# athf-er-acrylic.net
KiCad netlist of a schematic drawn in EAGLE
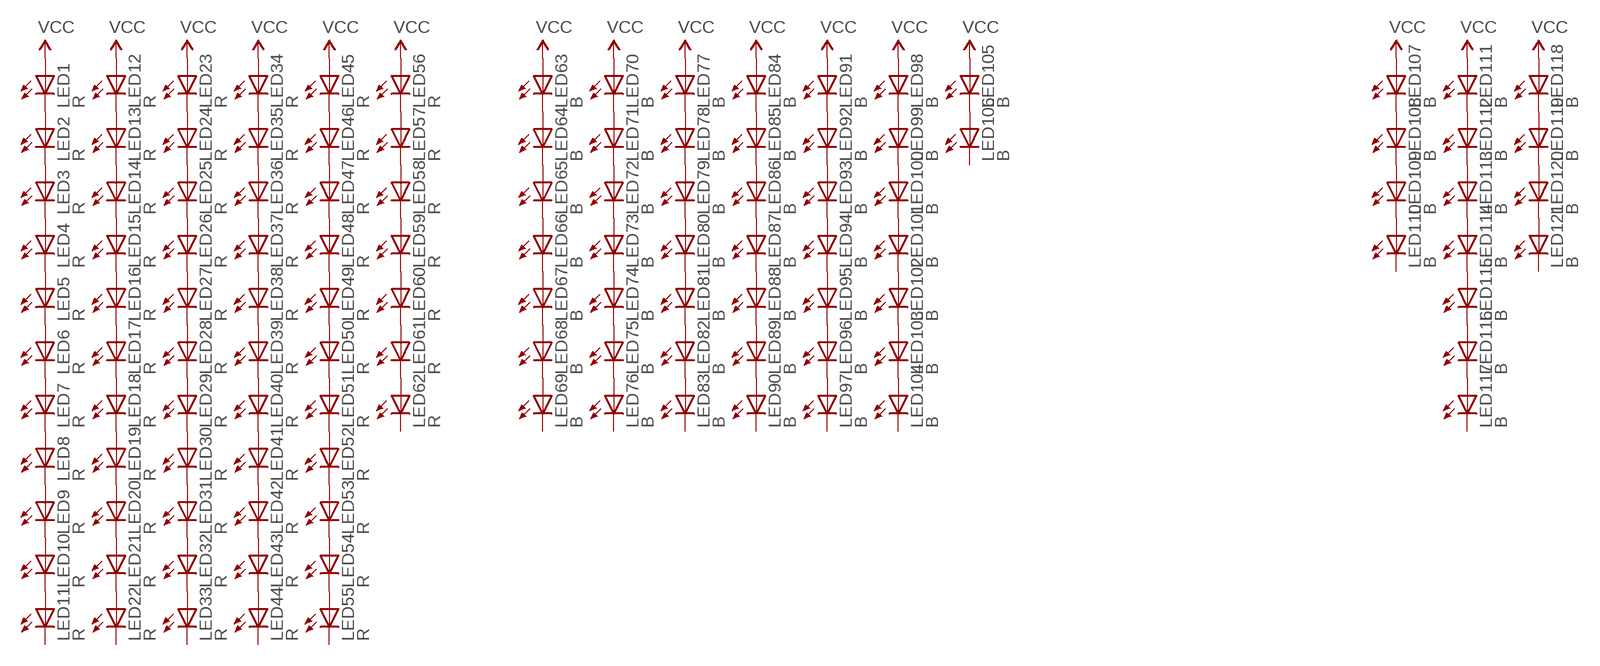
[diagram p0: schematic, sheet 1]

(export (version "E")
  (design (tool "Eeschema 10.0.6"))
  (components
    (comp (ref "LED1")
      (value "R")
      (footprint "eagle-import:LED5MMSQUARE")
      (libsource (lib "eagle-import") (part "LEDLED5MMSQUARE"))
    )
    (comp (ref "LED2")
      (value "R")
      (footprint "eagle-import:LED5MMSQUARE")
      (libsource (lib "eagle-import") (part "LEDLED5MMSQUARE"))
    )
    (comp (ref "LED3")
      (value "R")
      (footprint "eagle-import:LED5MMSQUARE")
      (libsource (lib "eagle-import") (part "LEDLED5MMSQUARE"))
    )
    (comp (ref "LED4")
      (value "R")
      (footprint "eagle-import:LED5MMSQUARE")
      (libsource (lib "eagle-import") (part "LEDLED5MMSQUARE"))
    )
    (comp (ref "LED5")
      (value "R")
      (footprint "eagle-import:LED5MMSQUARE")
      (libsource (lib "eagle-import") (part "LEDLED5MMSQUARE"))
    )
    (comp (ref "LED6")
      (value "R")
      (footprint "eagle-import:LED5MMSQUARE")
      (libsource (lib "eagle-import") (part "LEDLED5MMSQUARE"))
    )
    (comp (ref "LED7")
      (value "R")
      (footprint "eagle-import:LED5MMSQUARE")
      (libsource (lib "eagle-import") (part "LEDLED5MMSQUARE"))
    )
    (comp (ref "LED8")
      (value "R")
      (footprint "eagle-import:LED5MMSQUARE")
      (libsource (lib "eagle-import") (part "LEDLED5MMSQUARE"))
    )
    (comp (ref "LED9")
      (value "R")
      (footprint "eagle-import:LED5MMSQUARE")
      (libsource (lib "eagle-import") (part "LEDLED5MMSQUARE"))
    )
    (comp (ref "LED10")
      (value "R")
      (footprint "eagle-import:LED5MMSQUARE")
      (libsource (lib "eagle-import") (part "LEDLED5MMSQUARE"))
    )
    (comp (ref "LED11")
      (value "R")
      (footprint "eagle-import:LED5MMSQUARE")
      (libsource (lib "eagle-import") (part "LEDLED5MMSQUARE"))
    )
    (comp (ref "LED12")
      (value "R")
      (footprint "eagle-import:LED5MMSQUARE")
      (libsource (lib "eagle-import") (part "LEDLED5MMSQUARE"))
    )
    (comp (ref "LED13")
      (value "R")
      (footprint "eagle-import:LED5MMSQUARE")
      (libsource (lib "eagle-import") (part "LEDLED5MMSQUARE"))
    )
    (comp (ref "LED14")
      (value "R")
      (footprint "eagle-import:LED5MMSQUARE")
      (libsource (lib "eagle-import") (part "LEDLED5MMSQUARE"))
    )
    (comp (ref "LED15")
      (value "R")
      (footprint "eagle-import:LED5MMSQUARE")
      (libsource (lib "eagle-import") (part "LEDLED5MMSQUARE"))
    )
    (comp (ref "LED16")
      (value "R")
      (footprint "eagle-import:LED5MMSQUARE")
      (libsource (lib "eagle-import") (part "LEDLED5MMSQUARE"))
    )
    (comp (ref "LED17")
      (value "R")
      (footprint "eagle-import:LED5MMSQUARE")
      (libsource (lib "eagle-import") (part "LEDLED5MMSQUARE"))
    )
    (comp (ref "LED18")
      (value "R")
      (footprint "eagle-import:LED5MMSQUARE")
      (libsource (lib "eagle-import") (part "LEDLED5MMSQUARE"))
    )
    (comp (ref "LED19")
      (value "R")
      (footprint "eagle-import:LED5MMSQUARE")
      (libsource (lib "eagle-import") (part "LEDLED5MMSQUARE"))
    )
    (comp (ref "LED20")
      (value "R")
      (footprint "eagle-import:LED5MMSQUARE")
      (libsource (lib "eagle-import") (part "LEDLED5MMSQUARE"))
    )
    (comp (ref "LED21")
      (value "R")
      (footprint "eagle-import:LED5MMSQUARE")
      (libsource (lib "eagle-import") (part "LEDLED5MMSQUARE"))
    )
    (comp (ref "LED22")
      (value "R")
      (footprint "eagle-import:LED5MMSQUARE")
      (libsource (lib "eagle-import") (part "LEDLED5MMSQUARE"))
    )
    (comp (ref "LED23")
      (value "R")
      (footprint "eagle-import:LED5MMSQUARE")
      (libsource (lib "eagle-import") (part "LEDLED5MMSQUARE"))
    )
    (comp (ref "LED24")
      (value "R")
      (footprint "eagle-import:LED5MMSQUARE")
      (libsource (lib "eagle-import") (part "LEDLED5MMSQUARE"))
    )
    (comp (ref "LED25")
      (value "R")
      (footprint "eagle-import:LED5MMSQUARE")
      (libsource (lib "eagle-import") (part "LEDLED5MMSQUARE"))
    )
    (comp (ref "LED26")
      (value "R")
      (footprint "eagle-import:LED5MMSQUARE")
      (libsource (lib "eagle-import") (part "LEDLED5MMSQUARE"))
    )
    (comp (ref "LED27")
      (value "R")
      (footprint "eagle-import:LED5MMSQUARE")
      (libsource (lib "eagle-import") (part "LEDLED5MMSQUARE"))
    )
    (comp (ref "LED28")
      (value "R")
      (footprint "eagle-import:LED5MMSQUARE")
      (libsource (lib "eagle-import") (part "LEDLED5MMSQUARE"))
    )
    (comp (ref "LED29")
      (value "R")
      (footprint "eagle-import:LED5MMSQUARE")
      (libsource (lib "eagle-import") (part "LEDLED5MMSQUARE"))
    )
    (comp (ref "LED30")
      (value "R")
      (footprint "eagle-import:LED5MMSQUARE")
      (libsource (lib "eagle-import") (part "LEDLED5MMSQUARE"))
    )
    (comp (ref "LED31")
      (value "R")
      (footprint "eagle-import:LED5MMSQUARE")
      (libsource (lib "eagle-import") (part "LEDLED5MMSQUARE"))
    )
    (comp (ref "LED32")
      (value "R")
      (footprint "eagle-import:LED5MMSQUARE")
      (libsource (lib "eagle-import") (part "LEDLED5MMSQUARE"))
    )
    (comp (ref "LED33")
      (value "R")
      (footprint "eagle-import:LED5MMSQUARE")
      (libsource (lib "eagle-import") (part "LEDLED5MMSQUARE"))
    )
    (comp (ref "LED34")
      (value "R")
      (footprint "eagle-import:LED5MMSQUARE")
      (libsource (lib "eagle-import") (part "LEDLED5MMSQUARE"))
    )
    (comp (ref "LED35")
      (value "R")
      (footprint "eagle-import:LED5MMSQUARE")
      (libsource (lib "eagle-import") (part "LEDLED5MMSQUARE"))
    )
    (comp (ref "LED36")
      (value "R")
      (footprint "eagle-import:LED5MMSQUARE")
      (libsource (lib "eagle-import") (part "LEDLED5MMSQUARE"))
    )
    (comp (ref "LED37")
      (value "R")
      (footprint "eagle-import:LED5MMSQUARE")
      (libsource (lib "eagle-import") (part "LEDLED5MMSQUARE"))
    )
    (comp (ref "LED38")
      (value "R")
      (footprint "eagle-import:LED5MMSQUARE")
      (libsource (lib "eagle-import") (part "LEDLED5MMSQUARE"))
    )
    (comp (ref "LED39")
      (value "R")
      (footprint "eagle-import:LED5MMSQUARE")
      (libsource (lib "eagle-import") (part "LEDLED5MMSQUARE"))
    )
    (comp (ref "LED40")
      (value "R")
      (footprint "eagle-import:LED5MMSQUARE")
      (libsource (lib "eagle-import") (part "LEDLED5MMSQUARE"))
    )
    (comp (ref "LED41")
      (value "R")
      (footprint "eagle-import:LED5MMSQUARE")
      (libsource (lib "eagle-import") (part "LEDLED5MMSQUARE"))
    )
    (comp (ref "LED42")
      (value "R")
      (footprint "eagle-import:LED5MMSQUARE")
      (libsource (lib "eagle-import") (part "LEDLED5MMSQUARE"))
    )
    (comp (ref "LED43")
      (value "R")
      (footprint "eagle-import:LED5MMSQUARE")
      (libsource (lib "eagle-import") (part "LEDLED5MMSQUARE"))
    )
    (comp (ref "LED44")
      (value "R")
      (footprint "eagle-import:LED5MMSQUARE")
      (libsource (lib "eagle-import") (part "LEDLED5MMSQUARE"))
    )
    (comp (ref "LED45")
      (value "R")
      (footprint "eagle-import:LED5MMSQUARE")
      (libsource (lib "eagle-import") (part "LEDLED5MMSQUARE"))
    )
    (comp (ref "LED46")
      (value "R")
      (footprint "eagle-import:LED5MMSQUARE")
      (libsource (lib "eagle-import") (part "LEDLED5MMSQUARE"))
    )
    (comp (ref "LED47")
      (value "R")
      (footprint "eagle-import:LED5MMSQUARE")
      (libsource (lib "eagle-import") (part "LEDLED5MMSQUARE"))
    )
    (comp (ref "LED48")
      (value "R")
      (footprint "eagle-import:LED5MMSQUARE")
      (libsource (lib "eagle-import") (part "LEDLED5MMSQUARE"))
    )
    (comp (ref "LED49")
      (value "R")
      (footprint "eagle-import:LED5MMSQUARE")
      (libsource (lib "eagle-import") (part "LEDLED5MMSQUARE"))
    )
    (comp (ref "LED50")
      (value "R")
      (footprint "eagle-import:LED5MMSQUARE")
      (libsource (lib "eagle-import") (part "LEDLED5MMSQUARE"))
    )
    (comp (ref "LED51")
      (value "R")
      (footprint "eagle-import:LED5MMSQUARE")
      (libsource (lib "eagle-import") (part "LEDLED5MMSQUARE"))
    )
    (comp (ref "LED52")
      (value "R")
      (footprint "eagle-import:LED5MMSQUARE")
      (libsource (lib "eagle-import") (part "LEDLED5MMSQUARE"))
    )
    (comp (ref "LED53")
      (value "R")
      (footprint "eagle-import:LED5MMSQUARE")
      (libsource (lib "eagle-import") (part "LEDLED5MMSQUARE"))
    )
    (comp (ref "LED54")
      (value "R")
      (footprint "eagle-import:LED5MMSQUARE")
      (libsource (lib "eagle-import") (part "LEDLED5MMSQUARE"))
    )
    (comp (ref "LED55")
      (value "R")
      (footprint "eagle-import:LED5MMSQUARE")
      (libsource (lib "eagle-import") (part "LEDLED5MMSQUARE"))
    )
    (comp (ref "LED56")
      (value "R")
      (footprint "eagle-import:LED5MMSQUARE")
      (libsource (lib "eagle-import") (part "LEDLED5MMSQUARE"))
    )
    (comp (ref "LED57")
      (value "R")
      (footprint "eagle-import:LED5MMSQUARE")
      (libsource (lib "eagle-import") (part "LEDLED5MMSQUARE"))
    )
    (comp (ref "LED58")
      (value "R")
      (footprint "eagle-import:LED5MMSQUARE")
      (libsource (lib "eagle-import") (part "LEDLED5MMSQUARE"))
    )
    (comp (ref "LED59")
      (value "R")
      (footprint "eagle-import:LED5MMSQUARE")
      (libsource (lib "eagle-import") (part "LEDLED5MMSQUARE"))
    )
    (comp (ref "LED60")
      (value "R")
      (footprint "eagle-import:LED5MMSQUARE")
      (libsource (lib "eagle-import") (part "LEDLED5MMSQUARE"))
    )
    (comp (ref "LED61")
      (value "R")
      (footprint "eagle-import:LED5MMSQUARE")
      (libsource (lib "eagle-import") (part "LEDLED5MMSQUARE"))
    )
    (comp (ref "LED62")
      (value "R")
      (footprint "eagle-import:LED5MMSQUARE")
      (libsource (lib "eagle-import") (part "LEDLED5MMSQUARE"))
    )
    (comp (ref "LED63")
      (value "B")
      (footprint "eagle-import:LED5MMSQUARE")
      (libsource (lib "eagle-import") (part "LEDLED5MMSQUARE"))
    )
    (comp (ref "LED64")
      (value "B")
      (footprint "eagle-import:LED5MMSQUARE")
      (libsource (lib "eagle-import") (part "LEDLED5MMSQUARE"))
    )
    (comp (ref "LED65")
      (value "B")
      (footprint "eagle-import:LED5MMSQUARE")
      (libsource (lib "eagle-import") (part "LEDLED5MMSQUARE"))
    )
    (comp (ref "LED66")
      (value "B")
      (footprint "eagle-import:LED5MMSQUARE")
      (libsource (lib "eagle-import") (part "LEDLED5MMSQUARE"))
    )
    (comp (ref "LED67")
      (value "B")
      (footprint "eagle-import:LED5MMSQUARE")
      (libsource (lib "eagle-import") (part "LEDLED5MMSQUARE"))
    )
    (comp (ref "LED68")
      (value "B")
      (footprint "eagle-import:LED5MMSQUARE")
      (libsource (lib "eagle-import") (part "LEDLED5MMSQUARE"))
    )
    (comp (ref "LED69")
      (value "B")
      (footprint "eagle-import:LED5MMSQUARE")
      (libsource (lib "eagle-import") (part "LEDLED5MMSQUARE"))
    )
    (comp (ref "LED70")
      (value "B")
      (footprint "eagle-import:LED5MMSQUARE")
      (libsource (lib "eagle-import") (part "LEDLED5MMSQUARE"))
    )
    (comp (ref "LED71")
      (value "B")
      (footprint "eagle-import:LED5MMSQUARE")
      (libsource (lib "eagle-import") (part "LEDLED5MMSQUARE"))
    )
    (comp (ref "LED72")
      (value "B")
      (footprint "eagle-import:LED5MMSQUARE")
      (libsource (lib "eagle-import") (part "LEDLED5MMSQUARE"))
    )
    (comp (ref "LED73")
      (value "B")
      (footprint "eagle-import:LED5MMSQUARE")
      (libsource (lib "eagle-import") (part "LEDLED5MMSQUARE"))
    )
    (comp (ref "LED74")
      (value "B")
      (footprint "eagle-import:LED5MMSQUARE")
      (libsource (lib "eagle-import") (part "LEDLED5MMSQUARE"))
    )
    (comp (ref "LED75")
      (value "B")
      (footprint "eagle-import:LED5MMSQUARE")
      (libsource (lib "eagle-import") (part "LEDLED5MMSQUARE"))
    )
    (comp (ref "LED76")
      (value "B")
      (footprint "eagle-import:LED5MMSQUARE")
      (libsource (lib "eagle-import") (part "LEDLED5MMSQUARE"))
    )
    (comp (ref "LED77")
      (value "B")
      (footprint "eagle-import:LED5MMSQUARE")
      (libsource (lib "eagle-import") (part "LEDLED5MMSQUARE"))
    )
    (comp (ref "LED78")
      (value "B")
      (footprint "eagle-import:LED5MMSQUARE")
      (libsource (lib "eagle-import") (part "LEDLED5MMSQUARE"))
    )
    (comp (ref "LED79")
      (value "B")
      (footprint "eagle-import:LED5MMSQUARE")
      (libsource (lib "eagle-import") (part "LEDLED5MMSQUARE"))
    )
    (comp (ref "LED80")
      (value "B")
      (footprint "eagle-import:LED5MMSQUARE")
      (libsource (lib "eagle-import") (part "LEDLED5MMSQUARE"))
    )
    (comp (ref "LED81")
      (value "B")
      (footprint "eagle-import:LED5MMSQUARE")
      (libsource (lib "eagle-import") (part "LEDLED5MMSQUARE"))
    )
    (comp (ref "LED82")
      (value "B")
      (footprint "eagle-import:LED5MMSQUARE")
      (libsource (lib "eagle-import") (part "LEDLED5MMSQUARE"))
    )
    (comp (ref "LED83")
      (value "B")
      (footprint "eagle-import:LED5MMSQUARE")
      (libsource (lib "eagle-import") (part "LEDLED5MMSQUARE"))
    )
    (comp (ref "LED84")
      (value "B")
      (footprint "eagle-import:LED5MMSQUARE")
      (libsource (lib "eagle-import") (part "LEDLED5MMSQUARE"))
    )
    (comp (ref "LED85")
      (value "B")
      (footprint "eagle-import:LED5MMSQUARE")
      (libsource (lib "eagle-import") (part "LEDLED5MMSQUARE"))
    )
    (comp (ref "LED86")
      (value "B")
      (footprint "eagle-import:LED5MMSQUARE")
      (libsource (lib "eagle-import") (part "LEDLED5MMSQUARE"))
    )
    (comp (ref "LED87")
      (value "B")
      (footprint "eagle-import:LED5MMSQUARE")
      (libsource (lib "eagle-import") (part "LEDLED5MMSQUARE"))
    )
    (comp (ref "LED88")
      (value "B")
      (footprint "eagle-import:LED5MMSQUARE")
      (libsource (lib "eagle-import") (part "LEDLED5MMSQUARE"))
    )
    (comp (ref "LED89")
      (value "B")
      (footprint "eagle-import:LED5MMSQUARE")
      (libsource (lib "eagle-import") (part "LEDLED5MMSQUARE"))
    )
    (comp (ref "LED90")
      (value "B")
      (footprint "eagle-import:LED5MMSQUARE")
      (libsource (lib "eagle-import") (part "LEDLED5MMSQUARE"))
    )
    (comp (ref "LED91")
      (value "B")
      (footprint "eagle-import:LED5MMSQUARE")
      (libsource (lib "eagle-import") (part "LEDLED5MMSQUARE"))
    )
    (comp (ref "LED92")
      (value "B")
      (footprint "eagle-import:LED5MMSQUARE")
      (libsource (lib "eagle-import") (part "LEDLED5MMSQUARE"))
    )
    (comp (ref "LED93")
      (value "B")
      (footprint "eagle-import:LED5MMSQUARE")
      (libsource (lib "eagle-import") (part "LEDLED5MMSQUARE"))
    )
    (comp (ref "LED94")
      (value "B")
      (footprint "eagle-import:LED5MMSQUARE")
      (libsource (lib "eagle-import") (part "LEDLED5MMSQUARE"))
    )
    (comp (ref "LED95")
      (value "B")
      (footprint "eagle-import:LED5MMSQUARE")
      (libsource (lib "eagle-import") (part "LEDLED5MMSQUARE"))
    )
    (comp (ref "LED96")
      (value "B")
      (footprint "eagle-import:LED5MMSQUARE")
      (libsource (lib "eagle-import") (part "LEDLED5MMSQUARE"))
    )
    (comp (ref "LED97")
      (value "B")
      (footprint "eagle-import:LED5MMSQUARE")
      (libsource (lib "eagle-import") (part "LEDLED5MMSQUARE"))
    )
    (comp (ref "LED98")
      (value "B")
      (footprint "eagle-import:LED5MMSQUARE")
      (libsource (lib "eagle-import") (part "LEDLED5MMSQUARE"))
    )
    (comp (ref "LED99")
      (value "B")
      (footprint "eagle-import:LED5MMSQUARE")
      (libsource (lib "eagle-import") (part "LEDLED5MMSQUARE"))
    )
    (comp (ref "LED100")
      (value "B")
      (footprint "eagle-import:LED5MMSQUARE")
      (libsource (lib "eagle-import") (part "LEDLED5MMSQUARE"))
    )
    (comp (ref "LED101")
      (value "B")
      (footprint "eagle-import:LED5MMSQUARE")
      (libsource (lib "eagle-import") (part "LEDLED5MMSQUARE"))
    )
    (comp (ref "LED102")
      (value "B")
      (footprint "eagle-import:LED5MMSQUARE")
      (libsource (lib "eagle-import") (part "LEDLED5MMSQUARE"))
    )
    (comp (ref "LED103")
      (value "B")
      (footprint "eagle-import:LED5MMSQUARE")
      (libsource (lib "eagle-import") (part "LEDLED5MMSQUARE"))
    )
    (comp (ref "LED104")
      (value "B")
      (footprint "eagle-import:LED5MMSQUARE")
      (libsource (lib "eagle-import") (part "LEDLED5MMSQUARE"))
    )
    (comp (ref "LED105")
      (value "B")
      (footprint "eagle-import:LED5MMSQUARE")
      (libsource (lib "eagle-import") (part "LEDLED5MMSQUARE"))
    )
    (comp (ref "LED106")
      (value "B")
      (footprint "eagle-import:LED5MMSQUARE")
      (libsource (lib "eagle-import") (part "LEDLED5MMSQUARE"))
    )
    (comp (ref "LED107")
      (value "B")
      (footprint "eagle-import:LED5MMSQUARE")
      (libsource (lib "eagle-import") (part "LEDLED5MMSQUARE"))
    )
    (comp (ref "LED108")
      (value "B")
      (footprint "eagle-import:LED5MMSQUARE")
      (libsource (lib "eagle-import") (part "LEDLED5MMSQUARE"))
    )
    (comp (ref "LED109")
      (value "B")
      (footprint "eagle-import:LED5MMSQUARE")
      (libsource (lib "eagle-import") (part "LEDLED5MMSQUARE"))
    )
    (comp (ref "LED110")
      (value "B")
      (footprint "eagle-import:LED5MMSQUARE")
      (libsource (lib "eagle-import") (part "LEDLED5MMSQUARE"))
    )
    (comp (ref "LED111")
      (value "B")
      (footprint "eagle-import:LED5MMSQUARE")
      (libsource (lib "eagle-import") (part "LEDLED5MMSQUARE"))
    )
    (comp (ref "LED112")
      (value "B")
      (footprint "eagle-import:LED5MMSQUARE")
      (libsource (lib "eagle-import") (part "LEDLED5MMSQUARE"))
    )
    (comp (ref "LED113")
      (value "B")
      (footprint "eagle-import:LED5MMSQUARE")
      (libsource (lib "eagle-import") (part "LEDLED5MMSQUARE"))
    )
    (comp (ref "LED114")
      (value "B")
      (footprint "eagle-import:LED5MMSQUARE")
      (libsource (lib "eagle-import") (part "LEDLED5MMSQUARE"))
    )
    (comp (ref "LED115")
      (value "B")
      (footprint "eagle-import:LED5MMSQUARE")
      (libsource (lib "eagle-import") (part "LEDLED5MMSQUARE"))
    )
    (comp (ref "LED116")
      (value "B")
      (footprint "eagle-import:LED5MMSQUARE")
      (libsource (lib "eagle-import") (part "LEDLED5MMSQUARE"))
    )
    (comp (ref "LED117")
      (value "B")
      (footprint "eagle-import:LED5MMSQUARE")
      (libsource (lib "eagle-import") (part "LEDLED5MMSQUARE"))
    )
    (comp (ref "LED118")
      (value "B")
      (footprint "eagle-import:LED5MMSQUARE")
      (libsource (lib "eagle-import") (part "LEDLED5MMSQUARE"))
    )
    (comp (ref "LED119")
      (value "B")
      (footprint "eagle-import:LED5MMSQUARE")
      (libsource (lib "eagle-import") (part "LEDLED5MMSQUARE"))
    )
    (comp (ref "LED120")
      (value "B")
      (footprint "eagle-import:LED5MMSQUARE")
      (libsource (lib "eagle-import") (part "LEDLED5MMSQUARE"))
    )
    (comp (ref "LED121")
      (value "B")
      (footprint "eagle-import:LED5MMSQUARE")
      (libsource (lib "eagle-import") (part "LEDLED5MMSQUARE"))
    )
  )
  (nets
    (net (code "1") (name "Net-(LED1-C)") (class "Default")
      (node (ref "LED1") (pin "K") (pinfunction "C_K") (pintype "passive"))
      (node (ref "LED2") (pin "A") (pinfunction "A_A") (pintype "passive"))
    )
    (net (code "2") (name "Net-(LED2-C)") (class "Default")
      (node (ref "LED2") (pin "K") (pinfunction "C_K") (pintype "passive"))
      (node (ref "LED3") (pin "A") (pinfunction "A_A") (pintype "passive"))
    )
    (net (code "3") (name "Net-(LED3-C)") (class "Default")
      (node (ref "LED3") (pin "K") (pinfunction "C_K") (pintype "passive"))
      (node (ref "LED4") (pin "A") (pinfunction "A_A") (pintype "passive"))
    )
    (net (code "4") (name "Net-(LED4-C)") (class "Default")
      (node (ref "LED4") (pin "K") (pinfunction "C_K") (pintype "passive"))
      (node (ref "LED5") (pin "A") (pinfunction "A_A") (pintype "passive"))
    )
    (net (code "5") (name "Net-(LED5-C)") (class "Default")
      (node (ref "LED5") (pin "K") (pinfunction "C_K") (pintype "passive"))
      (node (ref "LED6") (pin "A") (pinfunction "A_A") (pintype "passive"))
    )
    (net (code "6") (name "Net-(LED6-C)") (class "Default")
      (node (ref "LED6") (pin "K") (pinfunction "C_K") (pintype "passive"))
      (node (ref "LED7") (pin "A") (pinfunction "A_A") (pintype "passive"))
    )
    (net (code "7") (name "Net-(LED7-C)") (class "Default")
      (node (ref "LED7") (pin "K") (pinfunction "C_K") (pintype "passive"))
      (node (ref "LED8") (pin "A") (pinfunction "A_A") (pintype "passive"))
    )
    (net (code "8") (name "Net-(LED8-C)") (class "Default")
      (node (ref "LED8") (pin "K") (pinfunction "C_K") (pintype "passive"))
      (node (ref "LED9") (pin "A") (pinfunction "A_A") (pintype "passive"))
    )
    (net (code "9") (name "Net-(LED9-C)") (class "Default")
      (node (ref "LED10") (pin "A") (pinfunction "A_A") (pintype "passive"))
      (node (ref "LED9") (pin "K") (pinfunction "C_K") (pintype "passive"))
    )
    (net (code "10") (name "Net-(LED10-C)") (class "Default")
      (node (ref "LED10") (pin "K") (pinfunction "C_K") (pintype "passive"))
      (node (ref "LED11") (pin "A") (pinfunction "A_A") (pintype "passive"))
    )
    (net (code "11") (name "Net-(LED12-C)") (class "Default")
      (node (ref "LED12") (pin "K") (pinfunction "C_K") (pintype "passive"))
      (node (ref "LED13") (pin "A") (pinfunction "A_A") (pintype "passive"))
    )
    (net (code "12") (name "Net-(LED13-C)") (class "Default")
      (node (ref "LED13") (pin "K") (pinfunction "C_K") (pintype "passive"))
      (node (ref "LED14") (pin "A") (pinfunction "A_A") (pintype "passive"))
    )
    (net (code "13") (name "Net-(LED14-C)") (class "Default")
      (node (ref "LED14") (pin "K") (pinfunction "C_K") (pintype "passive"))
      (node (ref "LED15") (pin "A") (pinfunction "A_A") (pintype "passive"))
    )
    (net (code "14") (name "Net-(LED15-C)") (class "Default")
      (node (ref "LED15") (pin "K") (pinfunction "C_K") (pintype "passive"))
      (node (ref "LED16") (pin "A") (pinfunction "A_A") (pintype "passive"))
    )
    (net (code "15") (name "Net-(LED16-C)") (class "Default")
      (node (ref "LED16") (pin "K") (pinfunction "C_K") (pintype "passive"))
      (node (ref "LED17") (pin "A") (pinfunction "A_A") (pintype "passive"))
    )
    (net (code "16") (name "Net-(LED17-C)") (class "Default")
      (node (ref "LED17") (pin "K") (pinfunction "C_K") (pintype "passive"))
      (node (ref "LED18") (pin "A") (pinfunction "A_A") (pintype "passive"))
    )
    (net (code "17") (name "Net-(LED18-C)") (class "Default")
      (node (ref "LED18") (pin "K") (pinfunction "C_K") (pintype "passive"))
      (node (ref "LED19") (pin "A") (pinfunction "A_A") (pintype "passive"))
    )
    (net (code "18") (name "Net-(LED19-C)") (class "Default")
      (node (ref "LED19") (pin "K") (pinfunction "C_K") (pintype "passive"))
      (node (ref "LED20") (pin "A") (pinfunction "A_A") (pintype "passive"))
    )
    (net (code "19") (name "Net-(LED20-C)") (class "Default")
      (node (ref "LED20") (pin "K") (pinfunction "C_K") (pintype "passive"))
      (node (ref "LED21") (pin "A") (pinfunction "A_A") (pintype "passive"))
    )
    (net (code "20") (name "Net-(LED21-C)") (class "Default")
      (node (ref "LED21") (pin "K") (pinfunction "C_K") (pintype "passive"))
      (node (ref "LED22") (pin "A") (pinfunction "A_A") (pintype "passive"))
    )
    (net (code "21") (name "Net-(LED23-C)") (class "Default")
      (node (ref "LED23") (pin "K") (pinfunction "C_K") (pintype "passive"))
      (node (ref "LED24") (pin "A") (pinfunction "A_A") (pintype "passive"))
    )
    (net (code "22") (name "Net-(LED24-C)") (class "Default")
      (node (ref "LED24") (pin "K") (pinfunction "C_K") (pintype "passive"))
      (node (ref "LED25") (pin "A") (pinfunction "A_A") (pintype "passive"))
    )
    (net (code "23") (name "Net-(LED25-C)") (class "Default")
      (node (ref "LED25") (pin "K") (pinfunction "C_K") (pintype "passive"))
      (node (ref "LED26") (pin "A") (pinfunction "A_A") (pintype "passive"))
    )
    (net (code "24") (name "Net-(LED26-C)") (class "Default")
      (node (ref "LED26") (pin "K") (pinfunction "C_K") (pintype "passive"))
      (node (ref "LED27") (pin "A") (pinfunction "A_A") (pintype "passive"))
    )
    (net (code "25") (name "Net-(LED27-C)") (class "Default")
      (node (ref "LED27") (pin "K") (pinfunction "C_K") (pintype "passive"))
      (node (ref "LED28") (pin "A") (pinfunction "A_A") (pintype "passive"))
    )
    (net (code "26") (name "Net-(LED28-C)") (class "Default")
      (node (ref "LED28") (pin "K") (pinfunction "C_K") (pintype "passive"))
      (node (ref "LED29") (pin "A") (pinfunction "A_A") (pintype "passive"))
    )
    (net (code "27") (name "Net-(LED29-C)") (class "Default")
      (node (ref "LED29") (pin "K") (pinfunction "C_K") (pintype "passive"))
      (node (ref "LED30") (pin "A") (pinfunction "A_A") (pintype "passive"))
    )
    (net (code "28") (name "Net-(LED30-C)") (class "Default")
      (node (ref "LED30") (pin "K") (pinfunction "C_K") (pintype "passive"))
      (node (ref "LED31") (pin "A") (pinfunction "A_A") (pintype "passive"))
    )
    (net (code "29") (name "Net-(LED31-C)") (class "Default")
      (node (ref "LED31") (pin "K") (pinfunction "C_K") (pintype "passive"))
      (node (ref "LED32") (pin "A") (pinfunction "A_A") (pintype "passive"))
    )
    (net (code "30") (name "Net-(LED32-C)") (class "Default")
      (node (ref "LED32") (pin "K") (pinfunction "C_K") (pintype "passive"))
      (node (ref "LED33") (pin "A") (pinfunction "A_A") (pintype "passive"))
    )
    (net (code "31") (name "Net-(LED34-C)") (class "Default")
      (node (ref "LED34") (pin "K") (pinfunction "C_K") (pintype "passive"))
      (node (ref "LED35") (pin "A") (pinfunction "A_A") (pintype "passive"))
    )
    (net (code "32") (name "Net-(LED35-C)") (class "Default")
      (node (ref "LED35") (pin "K") (pinfunction "C_K") (pintype "passive"))
      (node (ref "LED36") (pin "A") (pinfunction "A_A") (pintype "passive"))
    )
    (net (code "33") (name "Net-(LED36-C)") (class "Default")
      (node (ref "LED36") (pin "K") (pinfunction "C_K") (pintype "passive"))
      (node (ref "LED37") (pin "A") (pinfunction "A_A") (pintype "passive"))
    )
    (net (code "34") (name "Net-(LED37-C)") (class "Default")
      (node (ref "LED37") (pin "K") (pinfunction "C_K") (pintype "passive"))
      (node (ref "LED38") (pin "A") (pinfunction "A_A") (pintype "passive"))
    )
    (net (code "35") (name "Net-(LED38-C)") (class "Default")
      (node (ref "LED38") (pin "K") (pinfunction "C_K") (pintype "passive"))
      (node (ref "LED39") (pin "A") (pinfunction "A_A") (pintype "passive"))
    )
    (net (code "36") (name "Net-(LED39-C)") (class "Default")
      (node (ref "LED39") (pin "K") (pinfunction "C_K") (pintype "passive"))
      (node (ref "LED40") (pin "A") (pinfunction "A_A") (pintype "passive"))
    )
    (net (code "37") (name "Net-(LED40-C)") (class "Default")
      (node (ref "LED40") (pin "K") (pinfunction "C_K") (pintype "passive"))
      (node (ref "LED41") (pin "A") (pinfunction "A_A") (pintype "passive"))
    )
    (net (code "38") (name "Net-(LED41-C)") (class "Default")
      (node (ref "LED41") (pin "K") (pinfunction "C_K") (pintype "passive"))
      (node (ref "LED42") (pin "A") (pinfunction "A_A") (pintype "passive"))
    )
    (net (code "39") (name "Net-(LED42-C)") (class "Default")
      (node (ref "LED42") (pin "K") (pinfunction "C_K") (pintype "passive"))
      (node (ref "LED43") (pin "A") (pinfunction "A_A") (pintype "passive"))
    )
    (net (code "40") (name "Net-(LED43-C)") (class "Default")
      (node (ref "LED43") (pin "K") (pinfunction "C_K") (pintype "passive"))
      (node (ref "LED44") (pin "A") (pinfunction "A_A") (pintype "passive"))
    )
    (net (code "41") (name "Net-(LED45-C)") (class "Default")
      (node (ref "LED45") (pin "K") (pinfunction "C_K") (pintype "passive"))
      (node (ref "LED46") (pin "A") (pinfunction "A_A") (pintype "passive"))
    )
    (net (code "42") (name "Net-(LED46-C)") (class "Default")
      (node (ref "LED46") (pin "K") (pinfunction "C_K") (pintype "passive"))
      (node (ref "LED47") (pin "A") (pinfunction "A_A") (pintype "passive"))
    )
    (net (code "43") (name "Net-(LED47-C)") (class "Default")
      (node (ref "LED47") (pin "K") (pinfunction "C_K") (pintype "passive"))
      (node (ref "LED48") (pin "A") (pinfunction "A_A") (pintype "passive"))
    )
    (net (code "44") (name "Net-(LED48-C)") (class "Default")
      (node (ref "LED48") (pin "K") (pinfunction "C_K") (pintype "passive"))
      (node (ref "LED49") (pin "A") (pinfunction "A_A") (pintype "passive"))
    )
    (net (code "45") (name "Net-(LED49-C)") (class "Default")
      (node (ref "LED49") (pin "K") (pinfunction "C_K") (pintype "passive"))
      (node (ref "LED50") (pin "A") (pinfunction "A_A") (pintype "passive"))
    )
    (net (code "46") (name "Net-(LED50-C)") (class "Default")
      (node (ref "LED50") (pin "K") (pinfunction "C_K") (pintype "passive"))
      (node (ref "LED51") (pin "A") (pinfunction "A_A") (pintype "passive"))
    )
    (net (code "47") (name "Net-(LED51-C)") (class "Default")
      (node (ref "LED51") (pin "K") (pinfunction "C_K") (pintype "passive"))
      (node (ref "LED52") (pin "A") (pinfunction "A_A") (pintype "passive"))
    )
    (net (code "48") (name "Net-(LED52-C)") (class "Default")
      (node (ref "LED52") (pin "K") (pinfunction "C_K") (pintype "passive"))
      (node (ref "LED53") (pin "A") (pinfunction "A_A") (pintype "passive"))
    )
    (net (code "49") (name "Net-(LED53-C)") (class "Default")
      (node (ref "LED53") (pin "K") (pinfunction "C_K") (pintype "passive"))
      (node (ref "LED54") (pin "A") (pinfunction "A_A") (pintype "passive"))
    )
    (net (code "50") (name "Net-(LED54-C)") (class "Default")
      (node (ref "LED54") (pin "K") (pinfunction "C_K") (pintype "passive"))
      (node (ref "LED55") (pin "A") (pinfunction "A_A") (pintype "passive"))
    )
    (net (code "51") (name "Net-(LED56-C)") (class "Default")
      (node (ref "LED56") (pin "K") (pinfunction "C_K") (pintype "passive"))
      (node (ref "LED57") (pin "A") (pinfunction "A_A") (pintype "passive"))
    )
    (net (code "52") (name "Net-(LED57-C)") (class "Default")
      (node (ref "LED57") (pin "K") (pinfunction "C_K") (pintype "passive"))
      (node (ref "LED58") (pin "A") (pinfunction "A_A") (pintype "passive"))
    )
    (net (code "53") (name "Net-(LED58-C)") (class "Default")
      (node (ref "LED58") (pin "K") (pinfunction "C_K") (pintype "passive"))
      (node (ref "LED59") (pin "A") (pinfunction "A_A") (pintype "passive"))
    )
    (net (code "54") (name "Net-(LED59-C)") (class "Default")
      (node (ref "LED59") (pin "K") (pinfunction "C_K") (pintype "passive"))
      (node (ref "LED60") (pin "A") (pinfunction "A_A") (pintype "passive"))
    )
    (net (code "55") (name "Net-(LED60-C)") (class "Default")
      (node (ref "LED60") (pin "K") (pinfunction "C_K") (pintype "passive"))
      (node (ref "LED61") (pin "A") (pinfunction "A_A") (pintype "passive"))
    )
    (net (code "56") (name "Net-(LED61-C)") (class "Default")
      (node (ref "LED61") (pin "K") (pinfunction "C_K") (pintype "passive"))
      (node (ref "LED62") (pin "A") (pinfunction "A_A") (pintype "passive"))
    )
    (net (code "57") (name "Net-(LED63-C)") (class "Default")
      (node (ref "LED63") (pin "K") (pinfunction "C_K") (pintype "passive"))
      (node (ref "LED64") (pin "A") (pinfunction "A_A") (pintype "passive"))
    )
    (net (code "58") (name "Net-(LED64-C)") (class "Default")
      (node (ref "LED64") (pin "K") (pinfunction "C_K") (pintype "passive"))
      (node (ref "LED65") (pin "A") (pinfunction "A_A") (pintype "passive"))
    )
    (net (code "59") (name "Net-(LED65-C)") (class "Default")
      (node (ref "LED65") (pin "K") (pinfunction "C_K") (pintype "passive"))
      (node (ref "LED66") (pin "A") (pinfunction "A_A") (pintype "passive"))
    )
    (net (code "60") (name "Net-(LED66-C)") (class "Default")
      (node (ref "LED66") (pin "K") (pinfunction "C_K") (pintype "passive"))
      (node (ref "LED67") (pin "A") (pinfunction "A_A") (pintype "passive"))
    )
    (net (code "61") (name "Net-(LED67-C)") (class "Default")
      (node (ref "LED67") (pin "K") (pinfunction "C_K") (pintype "passive"))
      (node (ref "LED68") (pin "A") (pinfunction "A_A") (pintype "passive"))
    )
    (net (code "62") (name "Net-(LED68-C)") (class "Default")
      (node (ref "LED68") (pin "K") (pinfunction "C_K") (pintype "passive"))
      (node (ref "LED69") (pin "A") (pinfunction "A_A") (pintype "passive"))
    )
    (net (code "63") (name "Net-(LED70-C)") (class "Default")
      (node (ref "LED70") (pin "K") (pinfunction "C_K") (pintype "passive"))
      (node (ref "LED71") (pin "A") (pinfunction "A_A") (pintype "passive"))
    )
    (net (code "64") (name "Net-(LED71-C)") (class "Default")
      (node (ref "LED71") (pin "K") (pinfunction "C_K") (pintype "passive"))
      (node (ref "LED72") (pin "A") (pinfunction "A_A") (pintype "passive"))
    )
    (net (code "65") (name "Net-(LED72-C)") (class "Default")
      (node (ref "LED72") (pin "K") (pinfunction "C_K") (pintype "passive"))
      (node (ref "LED73") (pin "A") (pinfunction "A_A") (pintype "passive"))
    )
    (net (code "66") (name "Net-(LED73-C)") (class "Default")
      (node (ref "LED73") (pin "K") (pinfunction "C_K") (pintype "passive"))
      (node (ref "LED74") (pin "A") (pinfunction "A_A") (pintype "passive"))
    )
    (net (code "67") (name "Net-(LED74-C)") (class "Default")
      (node (ref "LED74") (pin "K") (pinfunction "C_K") (pintype "passive"))
      (node (ref "LED75") (pin "A") (pinfunction "A_A") (pintype "passive"))
    )
    (net (code "68") (name "Net-(LED75-C)") (class "Default")
      (node (ref "LED75") (pin "K") (pinfunction "C_K") (pintype "passive"))
      (node (ref "LED76") (pin "A") (pinfunction "A_A") (pintype "passive"))
    )
    (net (code "69") (name "Net-(LED77-C)") (class "Default")
      (node (ref "LED77") (pin "K") (pinfunction "C_K") (pintype "passive"))
      (node (ref "LED78") (pin "A") (pinfunction "A_A") (pintype "passive"))
    )
    (net (code "70") (name "Net-(LED78-C)") (class "Default")
      (node (ref "LED78") (pin "K") (pinfunction "C_K") (pintype "passive"))
      (node (ref "LED79") (pin "A") (pinfunction "A_A") (pintype "passive"))
    )
    (net (code "71") (name "Net-(LED79-C)") (class "Default")
      (node (ref "LED79") (pin "K") (pinfunction "C_K") (pintype "passive"))
      (node (ref "LED80") (pin "A") (pinfunction "A_A") (pintype "passive"))
    )
    (net (code "72") (name "Net-(LED80-C)") (class "Default")
      (node (ref "LED80") (pin "K") (pinfunction "C_K") (pintype "passive"))
      (node (ref "LED81") (pin "A") (pinfunction "A_A") (pintype "passive"))
    )
    (net (code "73") (name "Net-(LED81-C)") (class "Default")
      (node (ref "LED81") (pin "K") (pinfunction "C_K") (pintype "passive"))
      (node (ref "LED82") (pin "A") (pinfunction "A_A") (pintype "passive"))
    )
    (net (code "74") (name "Net-(LED82-C)") (class "Default")
      (node (ref "LED82") (pin "K") (pinfunction "C_K") (pintype "passive"))
      (node (ref "LED83") (pin "A") (pinfunction "A_A") (pintype "passive"))
    )
    (net (code "75") (name "Net-(LED84-C)") (class "Default")
      (node (ref "LED84") (pin "K") (pinfunction "C_K") (pintype "passive"))
      (node (ref "LED85") (pin "A") (pinfunction "A_A") (pintype "passive"))
    )
    (net (code "76") (name "Net-(LED85-C)") (class "Default")
      (node (ref "LED85") (pin "K") (pinfunction "C_K") (pintype "passive"))
      (node (ref "LED86") (pin "A") (pinfunction "A_A") (pintype "passive"))
    )
    (net (code "77") (name "Net-(LED86-C)") (class "Default")
      (node (ref "LED86") (pin "K") (pinfunction "C_K") (pintype "passive"))
      (node (ref "LED87") (pin "A") (pinfunction "A_A") (pintype "passive"))
    )
    (net (code "78") (name "Net-(LED87-C)") (class "Default")
      (node (ref "LED87") (pin "K") (pinfunction "C_K") (pintype "passive"))
      (node (ref "LED88") (pin "A") (pinfunction "A_A") (pintype "passive"))
    )
    (net (code "79") (name "Net-(LED88-C)") (class "Default")
      (node (ref "LED88") (pin "K") (pinfunction "C_K") (pintype "passive"))
      (node (ref "LED89") (pin "A") (pinfunction "A_A") (pintype "passive"))
    )
    (net (code "80") (name "Net-(LED89-C)") (class "Default")
      (node (ref "LED89") (pin "K") (pinfunction "C_K") (pintype "passive"))
      (node (ref "LED90") (pin "A") (pinfunction "A_A") (pintype "passive"))
    )
    (net (code "81") (name "Net-(LED91-C)") (class "Default")
      (node (ref "LED91") (pin "K") (pinfunction "C_K") (pintype "passive"))
      (node (ref "LED92") (pin "A") (pinfunction "A_A") (pintype "passive"))
    )
    (net (code "82") (name "Net-(LED92-C)") (class "Default")
      (node (ref "LED92") (pin "K") (pinfunction "C_K") (pintype "passive"))
      (node (ref "LED93") (pin "A") (pinfunction "A_A") (pintype "passive"))
    )
    (net (code "83") (name "Net-(LED93-C)") (class "Default")
      (node (ref "LED93") (pin "K") (pinfunction "C_K") (pintype "passive"))
      (node (ref "LED94") (pin "A") (pinfunction "A_A") (pintype "passive"))
    )
    (net (code "84") (name "Net-(LED94-C)") (class "Default")
      (node (ref "LED94") (pin "K") (pinfunction "C_K") (pintype "passive"))
      (node (ref "LED95") (pin "A") (pinfunction "A_A") (pintype "passive"))
    )
    (net (code "85") (name "Net-(LED95-C)") (class "Default")
      (node (ref "LED95") (pin "K") (pinfunction "C_K") (pintype "passive"))
      (node (ref "LED96") (pin "A") (pinfunction "A_A") (pintype "passive"))
    )
    (net (code "86") (name "Net-(LED96-C)") (class "Default")
      (node (ref "LED96") (pin "K") (pinfunction "C_K") (pintype "passive"))
      (node (ref "LED97") (pin "A") (pinfunction "A_A") (pintype "passive"))
    )
    (net (code "87") (name "Net-(LED98-C)") (class "Default")
      (node (ref "LED98") (pin "K") (pinfunction "C_K") (pintype "passive"))
      (node (ref "LED99") (pin "A") (pinfunction "A_A") (pintype "passive"))
    )
    (net (code "88") (name "Net-(LED99-C)") (class "Default")
      (node (ref "LED100") (pin "A") (pinfunction "A_A") (pintype "passive"))
      (node (ref "LED99") (pin "K") (pinfunction "C_K") (pintype "passive"))
    )
    (net (code "89") (name "Net-(LED100-C)") (class "Default")
      (node (ref "LED100") (pin "K") (pinfunction "C_K") (pintype "passive"))
      (node (ref "LED101") (pin "A") (pinfunction "A_A") (pintype "passive"))
    )
    (net (code "90") (name "Net-(LED101-C)") (class "Default")
      (node (ref "LED101") (pin "K") (pinfunction "C_K") (pintype "passive"))
      (node (ref "LED102") (pin "A") (pinfunction "A_A") (pintype "passive"))
    )
    (net (code "91") (name "Net-(LED102-C)") (class "Default")
      (node (ref "LED102") (pin "K") (pinfunction "C_K") (pintype "passive"))
      (node (ref "LED103") (pin "A") (pinfunction "A_A") (pintype "passive"))
    )
    (net (code "92") (name "Net-(LED103-C)") (class "Default")
      (node (ref "LED103") (pin "K") (pinfunction "C_K") (pintype "passive"))
      (node (ref "LED104") (pin "A") (pinfunction "A_A") (pintype "passive"))
    )
    (net (code "93") (name "Net-(LED105-C)") (class "Default")
      (node (ref "LED105") (pin "K") (pinfunction "C_K") (pintype "passive"))
      (node (ref "LED106") (pin "A") (pinfunction "A_A") (pintype "passive"))
    )
    (net (code "94") (name "Net-(LED107-C)") (class "Default")
      (node (ref "LED107") (pin "K") (pinfunction "C_K") (pintype "passive"))
      (node (ref "LED108") (pin "A") (pinfunction "A_A") (pintype "passive"))
    )
    (net (code "95") (name "Net-(LED108-C)") (class "Default")
      (node (ref "LED108") (pin "K") (pinfunction "C_K") (pintype "passive"))
      (node (ref "LED109") (pin "A") (pinfunction "A_A") (pintype "passive"))
    )
    (net (code "96") (name "Net-(LED109-C)") (class "Default")
      (node (ref "LED109") (pin "K") (pinfunction "C_K") (pintype "passive"))
      (node (ref "LED110") (pin "A") (pinfunction "A_A") (pintype "passive"))
    )
    (net (code "97") (name "Net-(LED111-C)") (class "Default")
      (node (ref "LED111") (pin "K") (pinfunction "C_K") (pintype "passive"))
      (node (ref "LED112") (pin "A") (pinfunction "A_A") (pintype "passive"))
    )
    (net (code "98") (name "Net-(LED112-C)") (class "Default")
      (node (ref "LED112") (pin "K") (pinfunction "C_K") (pintype "passive"))
      (node (ref "LED113") (pin "A") (pinfunction "A_A") (pintype "passive"))
    )
    (net (code "99") (name "Net-(LED113-C)") (class "Default")
      (node (ref "LED113") (pin "K") (pinfunction "C_K") (pintype "passive"))
      (node (ref "LED114") (pin "A") (pinfunction "A_A") (pintype "passive"))
    )
    (net (code "100") (name "Net-(LED114-C)") (class "Default")
      (node (ref "LED114") (pin "K") (pinfunction "C_K") (pintype "passive"))
      (node (ref "LED115") (pin "A") (pinfunction "A_A") (pintype "passive"))
    )
    (net (code "101") (name "Net-(LED115-C)") (class "Default")
      (node (ref "LED115") (pin "K") (pinfunction "C_K") (pintype "passive"))
      (node (ref "LED116") (pin "A") (pinfunction "A_A") (pintype "passive"))
    )
    (net (code "102") (name "Net-(LED116-C)") (class "Default")
      (node (ref "LED116") (pin "K") (pinfunction "C_K") (pintype "passive"))
      (node (ref "LED117") (pin "A") (pinfunction "A_A") (pintype "passive"))
    )
    (net (code "103") (name "Net-(LED118-C)") (class "Default")
      (node (ref "LED118") (pin "K") (pinfunction "C_K") (pintype "passive"))
      (node (ref "LED119") (pin "A") (pinfunction "A_A") (pintype "passive"))
    )
    (net (code "104") (name "Net-(LED119-C)") (class "Default")
      (node (ref "LED119") (pin "K") (pinfunction "C_K") (pintype "passive"))
      (node (ref "LED120") (pin "A") (pinfunction "A_A") (pintype "passive"))
    )
    (net (code "105") (name "Net-(LED120-C)") (class "Default")
      (node (ref "LED120") (pin "K") (pinfunction "C_K") (pintype "passive"))
      (node (ref "LED121") (pin "A") (pinfunction "A_A") (pintype "passive"))
    )
    (net (code "106") (name "VCC") (class "Default")
      (node (ref "LED1") (pin "A") (pinfunction "A_A") (pintype "passive"))
      (node (ref "LED105") (pin "A") (pinfunction "A_A") (pintype "passive"))
      (node (ref "LED107") (pin "A") (pinfunction "A_A") (pintype "passive"))
      (node (ref "LED111") (pin "A") (pinfunction "A_A") (pintype "passive"))
      (node (ref "LED118") (pin "A") (pinfunction "A_A") (pintype "passive"))
      (node (ref "LED12") (pin "A") (pinfunction "A_A") (pintype "passive"))
      (node (ref "LED23") (pin "A") (pinfunction "A_A") (pintype "passive"))
      (node (ref "LED34") (pin "A") (pinfunction "A_A") (pintype "passive"))
      (node (ref "LED45") (pin "A") (pinfunction "A_A") (pintype "passive"))
      (node (ref "LED56") (pin "A") (pinfunction "A_A") (pintype "passive"))
      (node (ref "LED63") (pin "A") (pinfunction "A_A") (pintype "passive"))
      (node (ref "LED70") (pin "A") (pinfunction "A_A") (pintype "passive"))
      (node (ref "LED77") (pin "A") (pinfunction "A_A") (pintype "passive"))
      (node (ref "LED84") (pin "A") (pinfunction "A_A") (pintype "passive"))
      (node (ref "LED91") (pin "A") (pinfunction "A_A") (pintype "passive"))
      (node (ref "LED98") (pin "A") (pinfunction "A_A") (pintype "passive"))
    )
    (net (code "107") (name "unconnected-(LED11-C-PadK)") (class "Default")
      (node (ref "LED11") (pin "K") (pinfunction "C_K") (pintype "passive"))
    )
    (net (code "108") (name "unconnected-(LED22-C-PadK)") (class "Default")
      (node (ref "LED22") (pin "K") (pinfunction "C_K") (pintype "passive"))
    )
    (net (code "109") (name "unconnected-(LED33-C-PadK)") (class "Default")
      (node (ref "LED33") (pin "K") (pinfunction "C_K") (pintype "passive"))
    )
    (net (code "110") (name "unconnected-(LED44-C-PadK)") (class "Default")
      (node (ref "LED44") (pin "K") (pinfunction "C_K") (pintype "passive"))
    )
    (net (code "111") (name "unconnected-(LED55-C-PadK)") (class "Default")
      (node (ref "LED55") (pin "K") (pinfunction "C_K") (pintype "passive"))
    )
    (net (code "112") (name "unconnected-(LED62-C-PadK)") (class "Default")
      (node (ref "LED62") (pin "K") (pinfunction "C_K") (pintype "passive"))
    )
    (net (code "113") (name "unconnected-(LED69-C-PadK)") (class "Default")
      (node (ref "LED69") (pin "K") (pinfunction "C_K") (pintype "passive"))
    )
    (net (code "114") (name "unconnected-(LED76-C-PadK)") (class "Default")
      (node (ref "LED76") (pin "K") (pinfunction "C_K") (pintype "passive"))
    )
    (net (code "115") (name "unconnected-(LED83-C-PadK)") (class "Default")
      (node (ref "LED83") (pin "K") (pinfunction "C_K") (pintype "passive"))
    )
    (net (code "116") (name "unconnected-(LED90-C-PadK)") (class "Default")
      (node (ref "LED90") (pin "K") (pinfunction "C_K") (pintype "passive"))
    )
    (net (code "117") (name "unconnected-(LED97-C-PadK)") (class "Default")
      (node (ref "LED97") (pin "K") (pinfunction "C_K") (pintype "passive"))
    )
    (net (code "118") (name "unconnected-(LED104-C-PadK)") (class "Default")
      (node (ref "LED104") (pin "K") (pinfunction "C_K") (pintype "passive"))
    )
    (net (code "119") (name "unconnected-(LED106-C-PadK)") (class "Default")
      (node (ref "LED106") (pin "K") (pinfunction "C_K") (pintype "passive"))
    )
    (net (code "120") (name "unconnected-(LED110-C-PadK)") (class "Default")
      (node (ref "LED110") (pin "K") (pinfunction "C_K") (pintype "passive"))
    )
    (net (code "121") (name "unconnected-(LED117-C-PadK)") (class "Default")
      (node (ref "LED117") (pin "K") (pinfunction "C_K") (pintype "passive"))
    )
    (net (code "122") (name "unconnected-(LED121-C-PadK)") (class "Default")
      (node (ref "LED121") (pin "K") (pinfunction "C_K") (pintype "passive"))
    )
  )
)
